# Battery_Board_v3_0.net
KiCad netlist of a schematic drawn in EAGLE
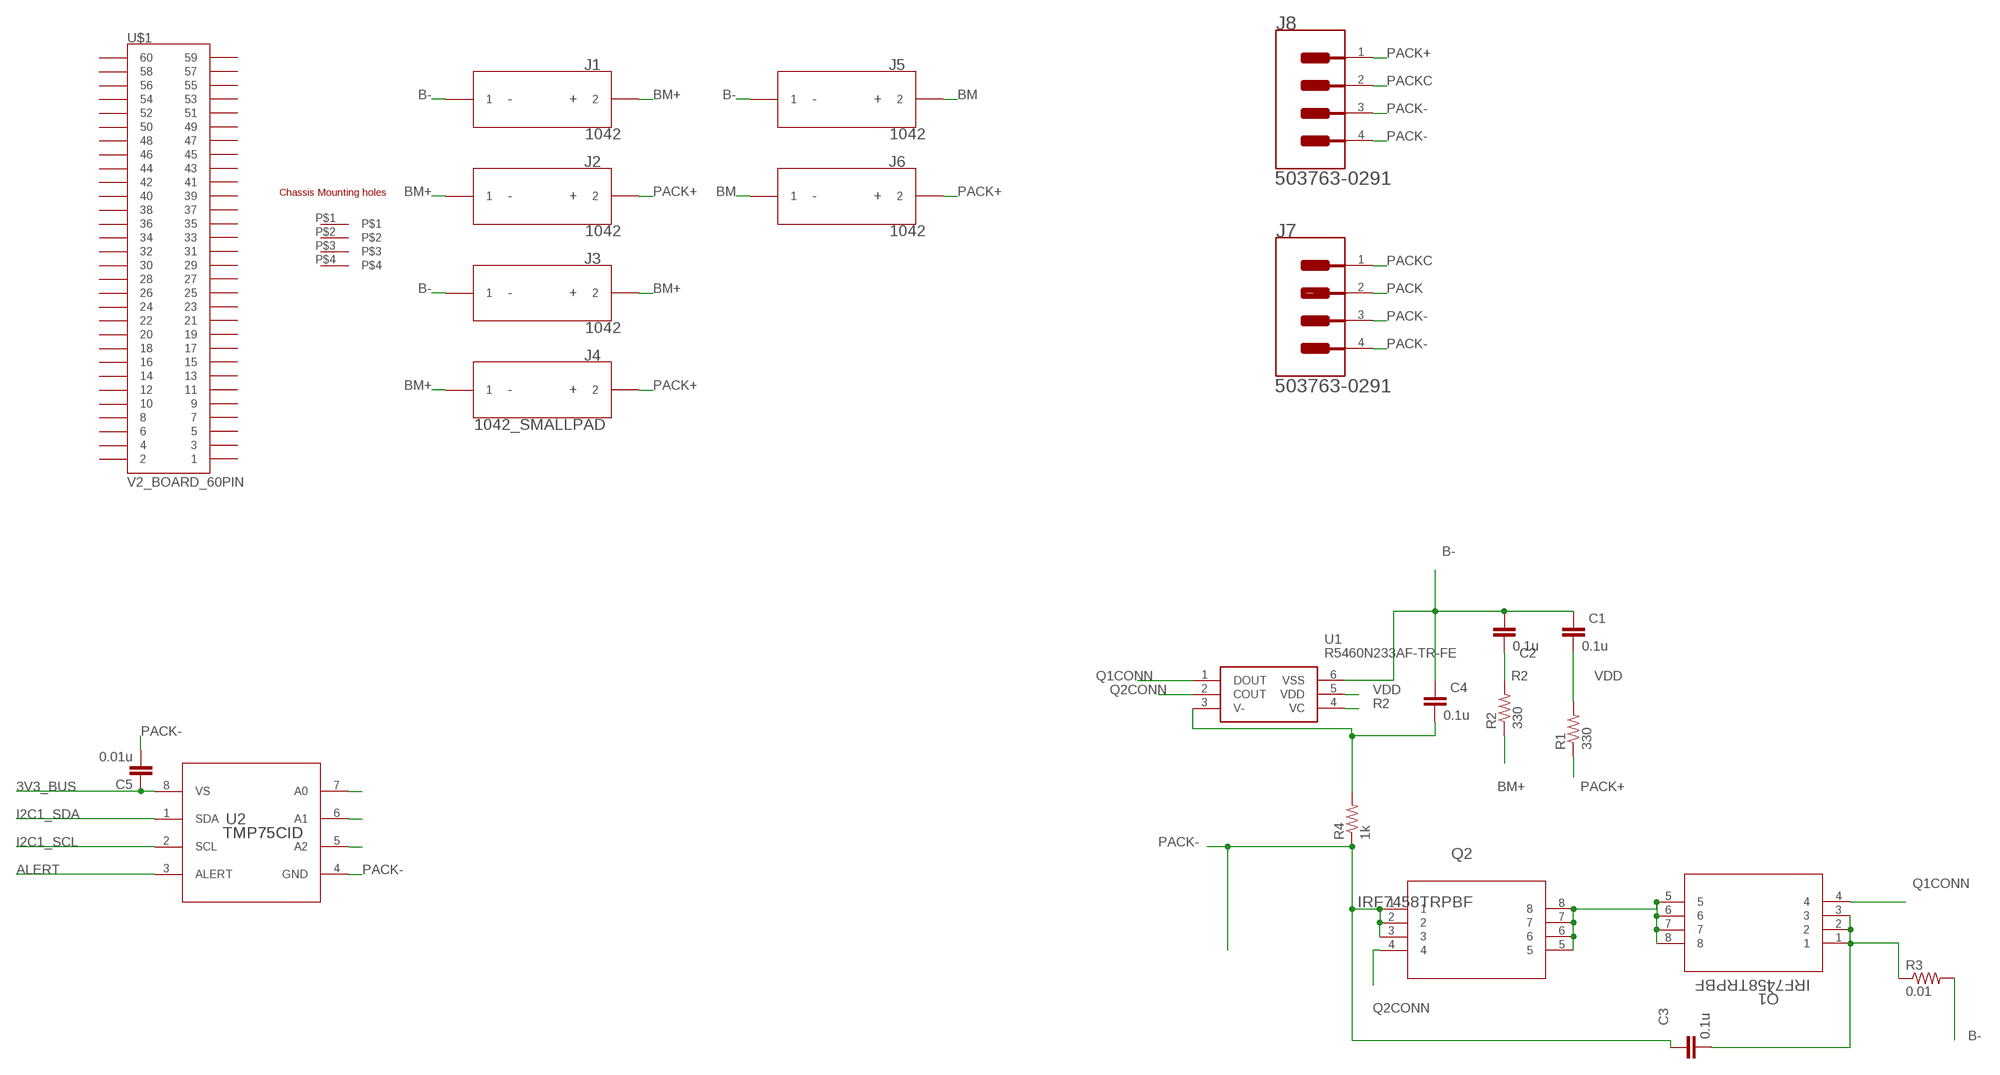
[diagram p0: schematic, sheet 1]

(export (version "E")
  (design (tool "Eeschema 10.0.6"))
  (components
    (comp (ref "C1")
      (value "0.1u")
      (footprint "eagle-import:0603-CAP")
      (libsource (lib "eagle-import") (part "CAP0603-CAP"))
    )
    (comp (ref "C2")
      (value "0.1u")
      (footprint "eagle-import:0603-CAP")
      (libsource (lib "eagle-import") (part "CAP0603-CAP"))
    )
    (comp (ref "C3")
      (value "0.1u")
      (footprint "eagle-import:0603-CAP")
      (libsource (lib "eagle-import") (part "CAP0603-CAP"))
    )
    (comp (ref "C4")
      (value "0.1u")
      (footprint "eagle-import:0603-CAP")
      (libsource (lib "eagle-import") (part "CAP0603-CAP"))
    )
    (comp (ref "C5")
      (value "0.01u")
      (footprint "eagle-import:0805")
      (libsource (lib "eagle-import") (part "CAP0805"))
    )
    (comp (ref "J1")
      (value "1042")
      (footprint "eagle-import:1042_KEY")
      (fields (field (name "COPYRIGHT") "Copyright (C) 2021 Ultra Librarian. All rights reserved."))
      (libsource (lib "eagle-import") (part "1042"))
    )
    (comp (ref "J2")
      (value "1042")
      (footprint "eagle-import:1042_KEY")
      (fields (field (name "COPYRIGHT") "Copyright (C) 2021 Ultra Librarian. All rights reserved."))
      (libsource (lib "eagle-import") (part "1042"))
    )
    (comp (ref "J3")
      (value "1042")
      (footprint "eagle-import:1042_KEY")
      (fields (field (name "COPYRIGHT") "Copyright (C) 2021 Ultra Librarian. All rights reserved."))
      (libsource (lib "eagle-import") (part "1042"))
    )
    (comp (ref "J4")
      (value "1042_SMALLPAD")
      (footprint "eagle-import:1042_KEY_SMALLPAD")
      (libsource (lib "eagle-import") (part "1042_SMALLPAD"))
    )
    (comp (ref "J5")
      (value "1042")
      (footprint "eagle-import:1042_KEY")
      (fields (field (name "COPYRIGHT") "Copyright (C) 2021 Ultra Librarian. All rights reserved."))
      (libsource (lib "eagle-import") (part "1042"))
    )
    (comp (ref "J6")
      (value "1042")
      (footprint "eagle-import:1042_KEY")
      (fields (field (name "COPYRIGHT") "Copyright (C) 2021 Ultra Librarian. All rights reserved."))
      (libsource (lib "eagle-import") (part "1042"))
    )
    (comp (ref "J7")
      (value "MOLEX_503763-0291MOLEX_503763-0291_0_0")
      (footprint "eagle-import:MOLEX_503763-0291_0")
      (fields
        (field (name "DIGIKEY_PART_NUMBER") "WM10654CT-ND")
        (field (name "MF") "Molex")
        (field (name "MOUSER_PART_NUMBER") "538-503763-0291")
      )
      (libsource (lib "eagle-import") (part "MOLEX_503763-0291MOLEX_503763-0291_0_0"))
    )
    (comp (ref "J8")
      (value "MOLEX_503763-0291MOLEX_503763-0291_0_0")
      (footprint "eagle-import:MOLEX_503763-0291_0")
      (fields
        (field (name "DIGIKEY_PART_NUMBER") "WM10654CT-ND")
        (field (name "MF") "Molex")
        (field (name "MOUSER_PART_NUMBER") "538-503763-0291")
      )
      (libsource (lib "eagle-import") (part "MOLEX_503763-0291MOLEX_503763-0291_0_0"))
    )
    (comp (ref "Q1")
      (value "IRF7458TRPBF")
      (footprint "eagle-import:SO-8_IRF7458_3P9X4P9_INF")
      (fields (field (name "COPYRIGHT") "Copyright (C) 2021 Ultra Librarian. All rights reserved."))
      (libsource (lib "eagle-import") (part "IRF7458TRPBF"))
    )
    (comp (ref "Q2")
      (value "IRF7458TRPBF")
      (footprint "eagle-import:SO-8_IRF7458_3P9X4P9_INF")
      (fields (field (name "COPYRIGHT") "Copyright (C) 2021 Ultra Librarian. All rights reserved."))
      (libsource (lib "eagle-import") (part "IRF7458TRPBF"))
    )
    (comp (ref "R1")
      (value "330")
      (footprint "eagle-import:0603-RES")
      (libsource (lib "eagle-import") (part "RESISTOR0603-RES"))
    )
    (comp (ref "R2")
      (value "330")
      (footprint "eagle-import:0603-RES")
      (libsource (lib "eagle-import") (part "RESISTOR0603-RES"))
    )
    (comp (ref "R3")
      (value "0.01")
      (footprint "eagle-import:R2512")
      (libsource (lib "eagle-import") (part "RESISTOR2512"))
    )
    (comp (ref "R4")
      (value "1k")
      (footprint "eagle-import:0603-RES")
      (libsource (lib "eagle-import") (part "RESISTOR0603-RES"))
    )
    (comp (ref "U$1")
      (value "V2_BOARD_60PIN")
      (footprint "eagle-import:PC104_WCONN_BACKPLANE_HEADER")
      (libsource (lib "eagle-import") (part "V2_BOARD_60PIN"))
    )
    (comp (ref "U1")
      (value "R5460N233AF-TR-FE")
      (footprint "eagle-import:SOT95P280X140-6N")
      (fields (field (name "MOUSER_PART_NUMBER") "848-R5460N233AFTRFE"))
      (libsource (lib "eagle-import") (part "R5460N233AF-TR-FE"))
    )
    (comp (ref "U2")
      (value "TMP75CID")
      (footprint "eagle-import:D0008A_N")
      (fields (field (name "COPYRIGHT") "Copyright (C) 2023 Ultra Librarian. All rights reserved."))
      (libsource (lib "eagle-import") (part "TMP75CID"))
    )
  )
  (nets
    (net (code "1") (name "/3V3_BUS") (class "Default")
      (node (ref "C5") (pin "1") (pinfunction "1_1") (pintype "passive"))
      (node (ref "U2") (pin "8") (pinfunction "VS_8") (pintype "power_in"))
    )
    (net (code "2") (name "/ALERT") (class "Default")
      (node (ref "U2") (pin "3") (pinfunction "ALERT_3") (pintype "open_collector"))
    )
    (net (code "3") (name "/B-") (class "Default")
      (node (ref "C1") (pin "1") (pinfunction "1_1") (pintype "passive"))
      (node (ref "C2") (pin "1") (pinfunction "1_1") (pintype "passive"))
      (node (ref "C4") (pin "1") (pinfunction "1_1") (pintype "passive"))
      (node (ref "J1") (pin "1") (pinfunction "1_1") (pintype "passive"))
      (node (ref "J3") (pin "1") (pinfunction "1_1") (pintype "passive"))
      (node (ref "J5") (pin "1") (pinfunction "1_1") (pintype "passive"))
      (node (ref "R3") (pin "2") (pinfunction "2_2") (pintype "passive"))
      (node (ref "U1") (pin "6") (pinfunction "VSS_6") (pintype "bidirectional"))
    )
    (net (code "4") (name "/BM") (class "Default")
      (node (ref "J5") (pin "2") (pinfunction "2_2") (pintype "passive"))
      (node (ref "J6") (pin "1") (pinfunction "1_1") (pintype "passive"))
    )
    (net (code "5") (name "/BM+") (class "Default")
      (node (ref "J1") (pin "2") (pinfunction "2_2") (pintype "passive"))
      (node (ref "J2") (pin "1") (pinfunction "1_1") (pintype "passive"))
      (node (ref "J3") (pin "2") (pinfunction "2_2") (pintype "passive"))
      (node (ref "J4") (pin "1") (pinfunction "1_1") (pintype "passive"))
      (node (ref "R2") (pin "1") (pinfunction "1_1") (pintype "passive"))
    )
    (net (code "6") (name "/I2C1_SCL") (class "Default")
      (node (ref "U2") (pin "2") (pinfunction "SCL_2") (pintype "input"))
    )
    (net (code "7") (name "/I2C1_SDA") (class "Default")
      (node (ref "U2") (pin "1") (pinfunction "SDA_1") (pintype "bidirectional"))
    )
    (net (code "8") (name "/PACK") (class "Default")
      (node (ref "J7") (pin "2") (pinfunction "2_2") (pintype "bidirectional"))
    )
    (net (code "9") (name "/PACK+") (class "Default")
      (node (ref "J2") (pin "2") (pinfunction "2_2") (pintype "passive"))
      (node (ref "J4") (pin "2") (pinfunction "2_2") (pintype "passive"))
      (node (ref "J6") (pin "2") (pinfunction "2_2") (pintype "passive"))
      (node (ref "J8") (pin "1") (pinfunction "1_1") (pintype "bidirectional"))
      (node (ref "R1") (pin "1") (pinfunction "1_1") (pintype "passive"))
    )
    (net (code "10") (name "/PACK-") (class "Default")
      (node (ref "C3") (pin "1") (pinfunction "1_1") (pintype "passive"))
      (node (ref "C5") (pin "2") (pinfunction "2_2") (pintype "passive"))
      (node (ref "J7") (pin "3") (pinfunction "MNT_1_3") (pintype "bidirectional"))
      (node (ref "J7") (pin "4") (pinfunction "MNT_2_4") (pintype "bidirectional"))
      (node (ref "J8") (pin "3") (pinfunction "MNT_1_3") (pintype "bidirectional"))
      (node (ref "J8") (pin "4") (pinfunction "MNT_2_4") (pintype "bidirectional"))
      (node (ref "Q2") (pin "1") (pinfunction "1_1") (pintype "passive"))
      (node (ref "Q2") (pin "2") (pinfunction "2_2") (pintype "passive"))
      (node (ref "Q2") (pin "3") (pinfunction "3_3") (pintype "passive"))
      (node (ref "R4") (pin "1") (pinfunction "1_1") (pintype "passive"))
      (node (ref "U2") (pin "4") (pinfunction "GND_4") (pintype "power_in"))
    )
    (net (code "11") (name "/PACKC") (class "Default")
      (node (ref "J7") (pin "1") (pinfunction "1_1") (pintype "bidirectional"))
      (node (ref "J8") (pin "2") (pinfunction "2_2") (pintype "bidirectional"))
    )
    (net (code "12") (name "/Q1CONN") (class "Default")
      (node (ref "Q1") (pin "4") (pinfunction "4_4") (pintype "passive"))
      (node (ref "U1") (pin "1") (pinfunction "DOUT_1") (pintype "bidirectional"))
    )
    (net (code "13") (name "/Q2CONN") (class "Default")
      (node (ref "Q2") (pin "4") (pinfunction "4_4") (pintype "passive"))
      (node (ref "U1") (pin "2") (pinfunction "COUT_2") (pintype "bidirectional"))
    )
    (net (code "14") (name "/R2") (class "Default")
      (node (ref "C2") (pin "2") (pinfunction "2_2") (pintype "passive"))
      (node (ref "R2") (pin "2") (pinfunction "2_2") (pintype "passive"))
      (node (ref "U1") (pin "4") (pinfunction "VC_4") (pintype "bidirectional"))
    )
    (net (code "15") (name "/VDD") (class "Default")
      (node (ref "C1") (pin "2") (pinfunction "2_2") (pintype "passive"))
      (node (ref "R1") (pin "2") (pinfunction "2_2") (pintype "passive"))
      (node (ref "U1") (pin "5") (pinfunction "VDD_5") (pintype "bidirectional"))
    )
    (net (code "16") (name "Net-(C3-Pad2)") (class "Default")
      (node (ref "C3") (pin "2") (pinfunction "2_2") (pintype "passive"))
      (node (ref "Q1") (pin "1") (pinfunction "1_1") (pintype "passive"))
      (node (ref "Q1") (pin "2") (pinfunction "2_2") (pintype "passive"))
      (node (ref "Q1") (pin "3") (pinfunction "3_3") (pintype "passive"))
      (node (ref "R3") (pin "1") (pinfunction "1_1") (pintype "passive"))
    )
    (net (code "17") (name "Net-(Q1-Pad5)") (class "Default")
      (node (ref "Q1") (pin "5") (pinfunction "5_5") (pintype "passive"))
      (node (ref "Q1") (pin "6") (pinfunction "6_6") (pintype "passive"))
      (node (ref "Q1") (pin "7") (pinfunction "7_7") (pintype "passive"))
      (node (ref "Q1") (pin "8") (pinfunction "8_8") (pintype "passive"))
      (node (ref "Q2") (pin "5") (pinfunction "5_5") (pintype "passive"))
      (node (ref "Q2") (pin "6") (pinfunction "6_6") (pintype "passive"))
      (node (ref "Q2") (pin "7") (pinfunction "7_7") (pintype "passive"))
      (node (ref "Q2") (pin "8") (pinfunction "8_8") (pintype "passive"))
    )
    (net (code "18") (name "Net-(U1-V-)") (class "Default")
      (node (ref "C4") (pin "2") (pinfunction "2_2") (pintype "passive"))
      (node (ref "R4") (pin "2") (pinfunction "2_2") (pintype "passive"))
      (node (ref "U1") (pin "3") (pinfunction "V-_3") (pintype "bidirectional"))
    )
    (net (code "19") (name "unconnected-(U$1-Pad1)") (class "Default")
      (node (ref "U$1") (pin "1") (pinfunction "1_1") (pintype "bidirectional"))
    )
    (net (code "20") (name "unconnected-(U$1-Pad2)") (class "Default")
      (node (ref "U$1") (pin "2") (pinfunction "2_2") (pintype "bidirectional"))
    )
    (net (code "21") (name "unconnected-(U$1-Pad3)") (class "Default")
      (node (ref "U$1") (pin "3") (pinfunction "3_3") (pintype "bidirectional"))
    )
    (net (code "22") (name "unconnected-(U$1-Pad4)") (class "Default")
      (node (ref "U$1") (pin "4") (pinfunction "4_4") (pintype "bidirectional"))
    )
    (net (code "23") (name "unconnected-(U$1-Pad5)") (class "Default")
      (node (ref "U$1") (pin "5") (pinfunction "5_5") (pintype "bidirectional"))
    )
    (net (code "24") (name "unconnected-(U$1-Pad6)") (class "Default")
      (node (ref "U$1") (pin "6") (pinfunction "6_6") (pintype "bidirectional"))
    )
    (net (code "25") (name "unconnected-(U$1-Pad7)") (class "Default")
      (node (ref "U$1") (pin "7") (pinfunction "7_7") (pintype "bidirectional"))
    )
    (net (code "26") (name "unconnected-(U$1-Pad8)") (class "Default")
      (node (ref "U$1") (pin "8") (pinfunction "8_8") (pintype "bidirectional"))
    )
    (net (code "27") (name "unconnected-(U$1-Pad9)") (class "Default")
      (node (ref "U$1") (pin "9") (pinfunction "9_9") (pintype "bidirectional"))
    )
    (net (code "28") (name "unconnected-(U$1-Pad10)") (class "Default")
      (node (ref "U$1") (pin "10") (pinfunction "10_10") (pintype "bidirectional"))
    )
    (net (code "29") (name "unconnected-(U$1-Pad11)") (class "Default")
      (node (ref "U$1") (pin "11") (pinfunction "11_11") (pintype "bidirectional"))
    )
    (net (code "30") (name "unconnected-(U$1-Pad12)") (class "Default")
      (node (ref "U$1") (pin "12") (pinfunction "12_12") (pintype "bidirectional"))
    )
    (net (code "31") (name "unconnected-(U$1-Pad13)") (class "Default")
      (node (ref "U$1") (pin "13") (pinfunction "13_13") (pintype "bidirectional"))
    )
    (net (code "32") (name "unconnected-(U$1-Pad14)") (class "Default")
      (node (ref "U$1") (pin "14") (pinfunction "14_14") (pintype "bidirectional"))
    )
    (net (code "33") (name "unconnected-(U$1-Pad15)") (class "Default")
      (node (ref "U$1") (pin "15") (pinfunction "15_15") (pintype "bidirectional"))
    )
    (net (code "34") (name "unconnected-(U$1-Pad16)") (class "Default")
      (node (ref "U$1") (pin "16") (pinfunction "16_16") (pintype "bidirectional"))
    )
    (net (code "35") (name "unconnected-(U$1-Pad17)") (class "Default")
      (node (ref "U$1") (pin "17") (pinfunction "17_17") (pintype "bidirectional"))
    )
    (net (code "36") (name "unconnected-(U$1-Pad18)") (class "Default")
      (node (ref "U$1") (pin "18") (pinfunction "18_18") (pintype "bidirectional"))
    )
    (net (code "37") (name "unconnected-(U$1-Pad19)") (class "Default")
      (node (ref "U$1") (pin "19") (pinfunction "19_19") (pintype "bidirectional"))
    )
    (net (code "38") (name "unconnected-(U$1-Pad20)") (class "Default")
      (node (ref "U$1") (pin "20") (pinfunction "20_20") (pintype "bidirectional"))
    )
    (net (code "39") (name "unconnected-(U$1-Pad21)") (class "Default")
      (node (ref "U$1") (pin "21") (pinfunction "21_21") (pintype "bidirectional"))
    )
    (net (code "40") (name "unconnected-(U$1-Pad22)") (class "Default")
      (node (ref "U$1") (pin "22") (pinfunction "22_22") (pintype "bidirectional"))
    )
    (net (code "41") (name "unconnected-(U$1-Pad23)") (class "Default")
      (node (ref "U$1") (pin "23") (pinfunction "23_23") (pintype "bidirectional"))
    )
    (net (code "42") (name "unconnected-(U$1-Pad24)") (class "Default")
      (node (ref "U$1") (pin "24") (pinfunction "24_24") (pintype "bidirectional"))
    )
    (net (code "43") (name "unconnected-(U$1-Pad25)") (class "Default")
      (node (ref "U$1") (pin "25") (pinfunction "25_25") (pintype "bidirectional"))
    )
    (net (code "44") (name "unconnected-(U$1-Pad26)") (class "Default")
      (node (ref "U$1") (pin "26") (pinfunction "26_26") (pintype "bidirectional"))
    )
    (net (code "45") (name "unconnected-(U$1-Pad27)") (class "Default")
      (node (ref "U$1") (pin "27") (pinfunction "27_27") (pintype "bidirectional"))
    )
    (net (code "46") (name "unconnected-(U$1-Pad28)") (class "Default")
      (node (ref "U$1") (pin "28") (pinfunction "28_28") (pintype "bidirectional"))
    )
    (net (code "47") (name "unconnected-(U$1-Pad29)") (class "Default")
      (node (ref "U$1") (pin "29") (pinfunction "29_29") (pintype "bidirectional"))
    )
    (net (code "48") (name "unconnected-(U$1-Pad30)") (class "Default")
      (node (ref "U$1") (pin "30") (pinfunction "30_30") (pintype "bidirectional"))
    )
    (net (code "49") (name "unconnected-(U$1-Pad31)") (class "Default")
      (node (ref "U$1") (pin "31") (pinfunction "31_31") (pintype "bidirectional"))
    )
    (net (code "50") (name "unconnected-(U$1-Pad32)") (class "Default")
      (node (ref "U$1") (pin "32") (pinfunction "32_32") (pintype "bidirectional"))
    )
    (net (code "51") (name "unconnected-(U$1-Pad33)") (class "Default")
      (node (ref "U$1") (pin "33") (pinfunction "33_33") (pintype "bidirectional"))
    )
    (net (code "52") (name "unconnected-(U$1-Pad34)") (class "Default")
      (node (ref "U$1") (pin "34") (pinfunction "34_34") (pintype "bidirectional"))
    )
    (net (code "53") (name "unconnected-(U$1-Pad35)") (class "Default")
      (node (ref "U$1") (pin "35") (pinfunction "35_35") (pintype "bidirectional"))
    )
    (net (code "54") (name "unconnected-(U$1-Pad36)") (class "Default")
      (node (ref "U$1") (pin "36") (pinfunction "36_36") (pintype "bidirectional"))
    )
    (net (code "55") (name "unconnected-(U$1-Pad37)") (class "Default")
      (node (ref "U$1") (pin "37") (pinfunction "37_37") (pintype "bidirectional"))
    )
    (net (code "56") (name "unconnected-(U$1-Pad38)") (class "Default")
      (node (ref "U$1") (pin "38") (pinfunction "38_38") (pintype "bidirectional"))
    )
    (net (code "57") (name "unconnected-(U$1-Pad39)") (class "Default")
      (node (ref "U$1") (pin "39") (pinfunction "39_39") (pintype "bidirectional"))
    )
    (net (code "58") (name "unconnected-(U$1-Pad40)") (class "Default")
      (node (ref "U$1") (pin "40") (pinfunction "40_40") (pintype "bidirectional"))
    )
    (net (code "59") (name "unconnected-(U$1-Pad41)") (class "Default")
      (node (ref "U$1") (pin "41") (pinfunction "41_41") (pintype "bidirectional"))
    )
    (net (code "60") (name "unconnected-(U$1-Pad42)") (class "Default")
      (node (ref "U$1") (pin "42") (pinfunction "42_42") (pintype "bidirectional"))
    )
    (net (code "61") (name "unconnected-(U$1-Pad43)") (class "Default")
      (node (ref "U$1") (pin "43") (pinfunction "43_43") (pintype "bidirectional"))
    )
    (net (code "62") (name "unconnected-(U$1-Pad44)") (class "Default")
      (node (ref "U$1") (pin "44") (pinfunction "44_44") (pintype "bidirectional"))
    )
    (net (code "63") (name "unconnected-(U$1-Pad45)") (class "Default")
      (node (ref "U$1") (pin "45") (pinfunction "45_45") (pintype "bidirectional"))
    )
    (net (code "64") (name "unconnected-(U$1-Pad46)") (class "Default")
      (node (ref "U$1") (pin "46") (pinfunction "46_46") (pintype "bidirectional"))
    )
    (net (code "65") (name "unconnected-(U$1-Pad47)") (class "Default")
      (node (ref "U$1") (pin "47") (pinfunction "47_47") (pintype "bidirectional"))
    )
    (net (code "66") (name "unconnected-(U$1-Pad48)") (class "Default")
      (node (ref "U$1") (pin "48") (pinfunction "48_48") (pintype "bidirectional"))
    )
    (net (code "67") (name "unconnected-(U$1-Pad49)") (class "Default")
      (node (ref "U$1") (pin "49") (pinfunction "49_49") (pintype "bidirectional"))
    )
    (net (code "68") (name "unconnected-(U$1-Pad50)") (class "Default")
      (node (ref "U$1") (pin "50") (pinfunction "50_50") (pintype "bidirectional"))
    )
    (net (code "69") (name "unconnected-(U$1-Pad51)") (class "Default")
      (node (ref "U$1") (pin "51") (pinfunction "51_51") (pintype "bidirectional"))
    )
    (net (code "70") (name "unconnected-(U$1-Pad52)") (class "Default")
      (node (ref "U$1") (pin "52") (pinfunction "52_52") (pintype "bidirectional"))
    )
    (net (code "71") (name "unconnected-(U$1-Pad53)") (class "Default")
      (node (ref "U$1") (pin "53") (pinfunction "53_53") (pintype "bidirectional"))
    )
    (net (code "72") (name "unconnected-(U$1-Pad54)") (class "Default")
      (node (ref "U$1") (pin "54") (pinfunction "54_54") (pintype "bidirectional"))
    )
    (net (code "73") (name "unconnected-(U$1-Pad55)") (class "Default")
      (node (ref "U$1") (pin "55") (pinfunction "55_55") (pintype "bidirectional"))
    )
    (net (code "74") (name "unconnected-(U$1-Pad56)") (class "Default")
      (node (ref "U$1") (pin "56") (pinfunction "56_56") (pintype "bidirectional"))
    )
    (net (code "75") (name "unconnected-(U$1-Pad57)") (class "Default")
      (node (ref "U$1") (pin "57") (pinfunction "57_57") (pintype "bidirectional"))
    )
    (net (code "76") (name "unconnected-(U$1-Pad58)") (class "Default")
      (node (ref "U$1") (pin "58") (pinfunction "58_58") (pintype "bidirectional"))
    )
    (net (code "77") (name "unconnected-(U$1-Pad59)") (class "Default")
      (node (ref "U$1") (pin "59") (pinfunction "59_59") (pintype "bidirectional"))
    )
    (net (code "78") (name "unconnected-(U$1-Pad60)") (class "Default")
      (node (ref "U$1") (pin "60") (pinfunction "60_60") (pintype "bidirectional"))
    )
    (net (code "79") (name "unconnected-(U$1-PadP$1)") (class "Default")
      (node (ref "U$1") (pin "P$1") (pinfunction "P$1_P$1") (pintype "bidirectional"))
    )
    (net (code "80") (name "unconnected-(U$1-PadP$2)") (class "Default")
      (node (ref "U$1") (pin "P$2") (pinfunction "P$2_P$2") (pintype "bidirectional"))
    )
    (net (code "81") (name "unconnected-(U$1-PadP$3)") (class "Default")
      (node (ref "U$1") (pin "P$3") (pinfunction "P$3_P$3") (pintype "bidirectional"))
    )
    (net (code "82") (name "unconnected-(U$1-PadP$4)") (class "Default")
      (node (ref "U$1") (pin "P$4") (pinfunction "P$4_P$4") (pintype "bidirectional"))
    )
    (net (code "83") (name "unconnected-(U2-A0-Pad7)") (class "Default")
      (node (ref "U2") (pin "7") (pinfunction "A0_7") (pintype "input"))
    )
    (net (code "84") (name "unconnected-(U2-A1-Pad6)") (class "Default")
      (node (ref "U2") (pin "6") (pinfunction "A1_6") (pintype "input"))
    )
    (net (code "85") (name "unconnected-(U2-A2-Pad5)") (class "Default")
      (node (ref "U2") (pin "5") (pinfunction "A2_5") (pintype "input"))
    )
  )
)
